# mailbox.net
KiCad netlist of a schematic drawn in EAGLE
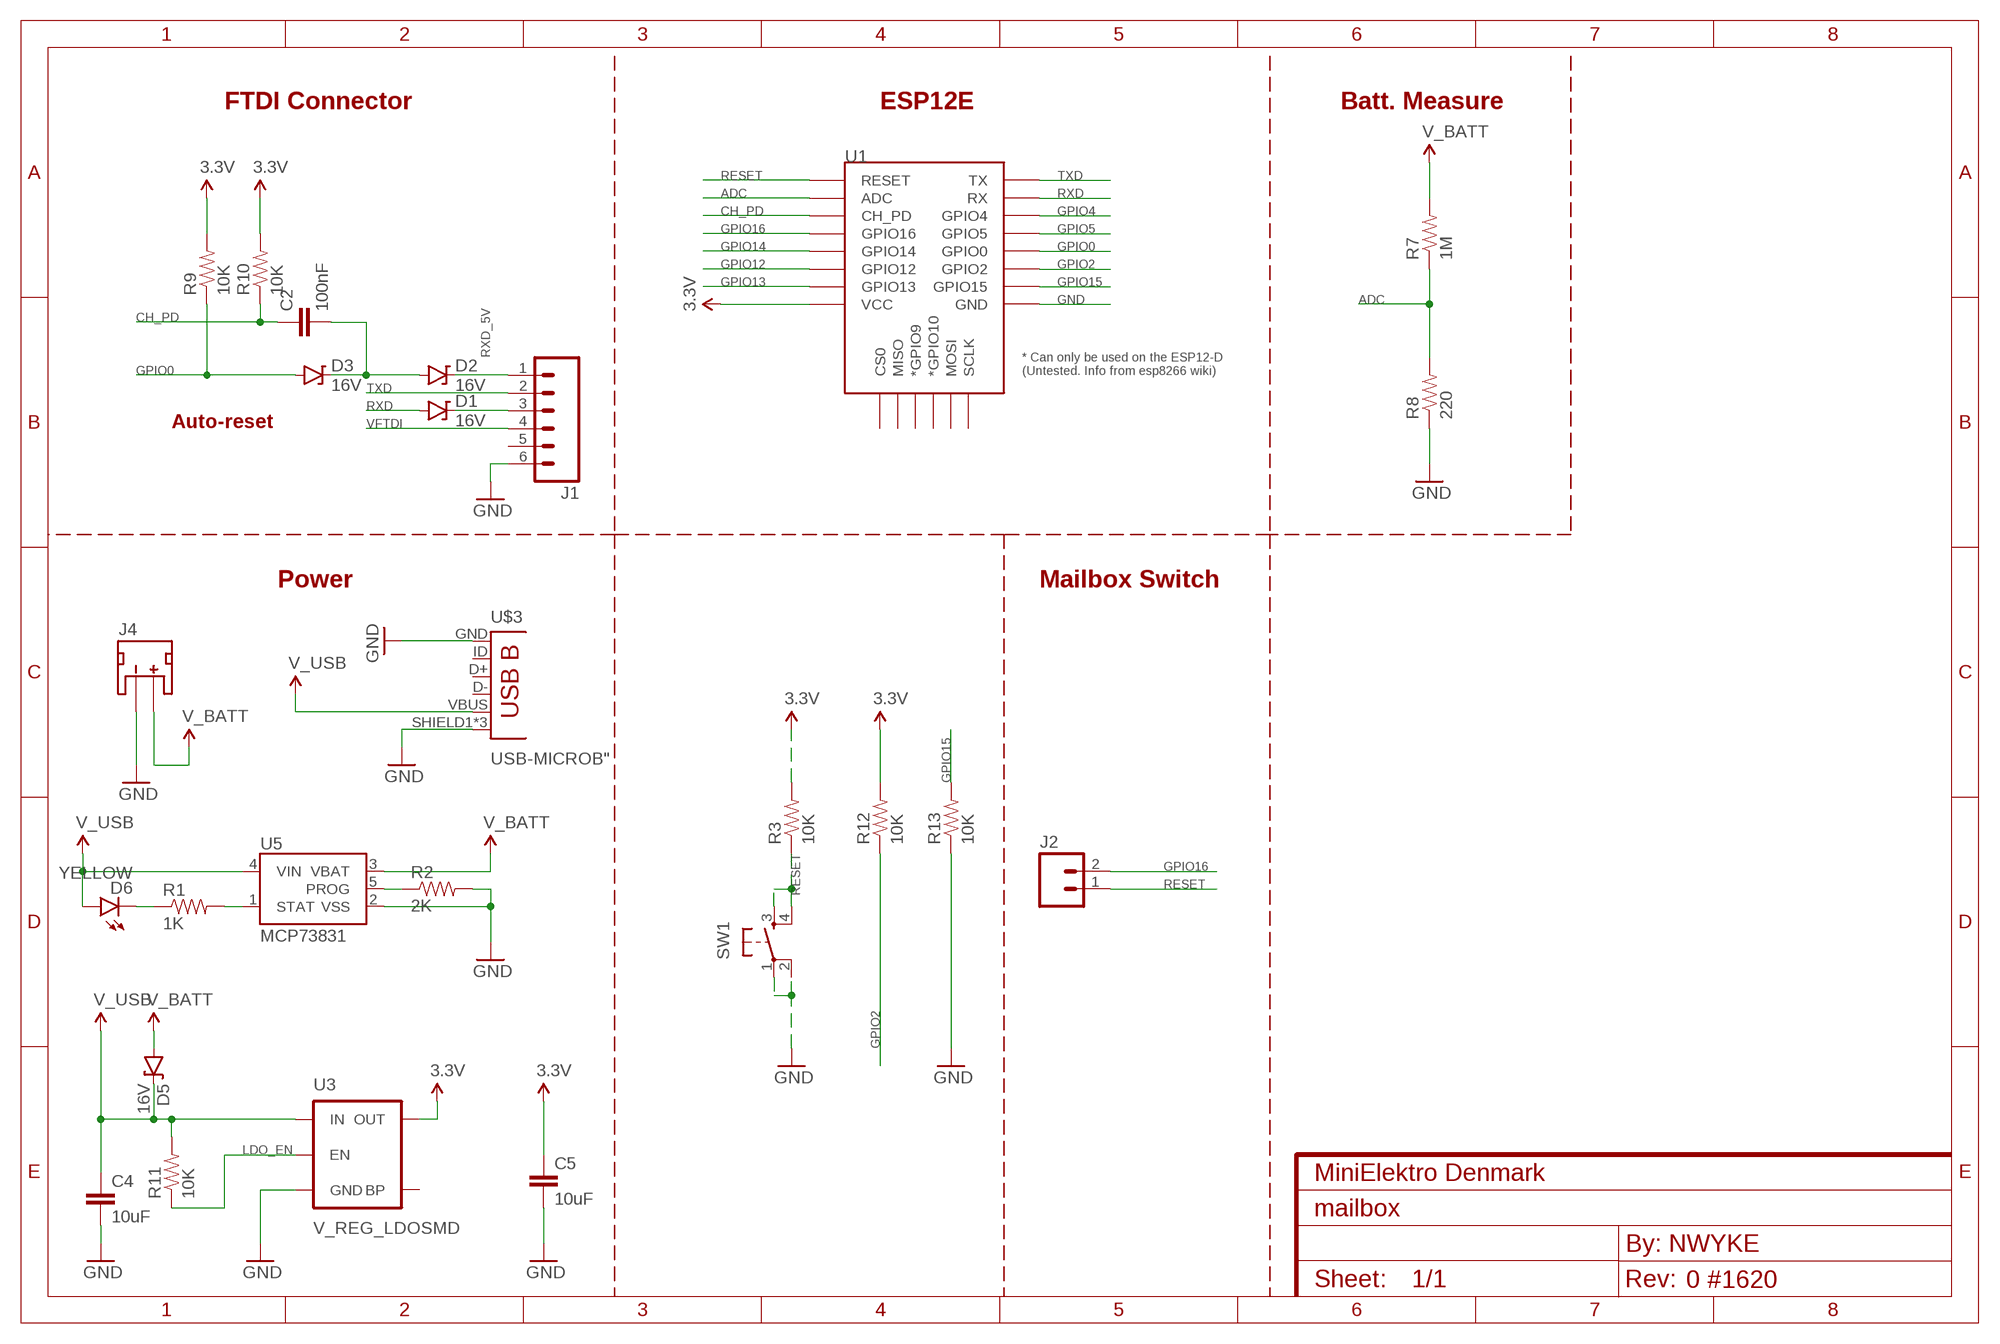
[diagram p0: schematic, sheet 1]

(export (version "E")
  (design (tool "Eeschema 10.0.6"))
  (components
    (comp (ref "C2")
      (value "100nF")
      (footprint "eagle-import:1206")
      (libsource (lib "eagle-import") (part "CAP1206"))
    )
    (comp (ref "C4")
      (value "10uF")
      (footprint "eagle-import:1206")
      (libsource (lib "eagle-import") (part "CAP1206"))
    )
    (comp (ref "C5")
      (value "10uF")
      (footprint "eagle-import:1206")
      (libsource (lib "eagle-import") (part "CAP1206"))
    )
    (comp (ref "D1")
      (value "16V")
      (footprint "eagle-import:SOD-123")
      (libsource (lib "eagle-import") (part "DIODE-ZENER16V"))
    )
    (comp (ref "D2")
      (value "16V")
      (footprint "eagle-import:SOD-123")
      (libsource (lib "eagle-import") (part "DIODE-ZENER16V"))
    )
    (comp (ref "D3")
      (value "16V")
      (footprint "eagle-import:SOD-123")
      (libsource (lib "eagle-import") (part "DIODE-ZENER16V"))
    )
    (comp (ref "D5")
      (value "16V")
      (footprint "eagle-import:SOD-123")
      (libsource (lib "eagle-import") (part "DIODE-ZENER16V"))
    )
    (comp (ref "D6")
      (value "YELLOW")
      (footprint "eagle-import:LED-1206")
      (libsource (lib "eagle-import") (part "LED-YELLOW1206"))
    )
    (comp (ref "J1")
      (value "M06SILK_FEMALE_PTH")
      (footprint "eagle-import:1X06")
      (libsource (lib "eagle-import") (part "M06SILK_FEMALE_PTH"))
    )
    (comp (ref "J2")
      (value "M02LOCK")
      (footprint "eagle-import:1X02_LOCK")
      (libsource (lib "eagle-import") (part "M02LOCK"))
    )
    (comp (ref "J4")
      (value "JST_2MM_MALE")
      (footprint "eagle-import:JST-2-SMD")
      (libsource (lib "eagle-import") (part "JST_2MM_MALE"))
    )
    (comp (ref "R1")
      (value "1K")
      (footprint "eagle-import:1206")
      (libsource (lib "eagle-import") (part "RESISTOR1206"))
    )
    (comp (ref "R2")
      (value "2K")
      (footprint "eagle-import:1206")
      (libsource (lib "eagle-import") (part "RESISTOR1206"))
    )
    (comp (ref "R3")
      (value "10K")
      (footprint "eagle-import:1206")
      (libsource (lib "eagle-import") (part "RESISTOR1206"))
    )
    (comp (ref "R7")
      (value "1M")
      (footprint "eagle-import:1206")
      (libsource (lib "eagle-import") (part "RESISTOR1206"))
    )
    (comp (ref "R8")
      (value "220")
      (footprint "eagle-import:1206")
      (libsource (lib "eagle-import") (part "RESISTOR1206"))
    )
    (comp (ref "R9")
      (value "10K")
      (footprint "eagle-import:1206")
      (libsource (lib "eagle-import") (part "RESISTOR1206"))
    )
    (comp (ref "R10")
      (value "10K")
      (footprint "eagle-import:1206")
      (libsource (lib "eagle-import") (part "RESISTOR1206"))
    )
    (comp (ref "R11")
      (value "10K")
      (footprint "eagle-import:1206")
      (libsource (lib "eagle-import") (part "RESISTOR1206"))
    )
    (comp (ref "R12")
      (value "10K")
      (footprint "eagle-import:1206")
      (libsource (lib "eagle-import") (part "RESISTOR1206"))
    )
    (comp (ref "R13")
      (value "10K")
      (footprint "eagle-import:1206")
      (libsource (lib "eagle-import") (part "RESISTOR1206"))
    )
    (comp (ref "SW1")
      (value "SWITCH_SPST_4_PINRECT")
      (footprint "eagle-import:TACTILE_SWITCH_SMD_4.6X2.8MM")
      (libsource (lib "eagle-import") (part "SWITCH_SPST_4_PINRECT"))
    )
    (comp (ref "U$3")
      (value "USB-MICROB\"")
      (footprint "eagle-import:USB-B-MICRO-SMD_V03")
      (libsource (lib "eagle-import") (part "USB-MICROB{dblquote}"))
    )
    (comp (ref "U1")
      (value "ESP12ESMD")
      (footprint "eagle-import:ESP12E-SMD")
      (libsource (lib "eagle-import") (part "ESP12ESMD"))
    )
    (comp (ref "U3")
      (value "V_REG_LDOSMD")
      (footprint "eagle-import:SOT23-5")
      (libsource (lib "eagle-import") (part "V_REG_LDOSMD"))
    )
    (comp (ref "U5")
      (value "MCP73831")
      (footprint "eagle-import:SOT23-5")
      (libsource (lib "eagle-import") (part "MCP73831"))
    )
  )
  (nets
    (net (code "1") (name "/ADC") (class "Default")
      (node (ref "R7") (pin "1") (pinfunction "1_1") (pintype "passive"))
      (node (ref "R8") (pin "2") (pinfunction "2_2") (pintype "passive"))
      (node (ref "U1") (pin "ADC") (pinfunction "ADC_ADC") (pintype "bidirectional"))
    )
    (net (code "2") (name "/CH_PD") (class "Default")
      (node (ref "C2") (pin "1") (pinfunction "1_1") (pintype "passive"))
      (node (ref "R10") (pin "1") (pinfunction "1_1") (pintype "passive"))
      (node (ref "U1") (pin "CH_PD") (pinfunction "CH_PD_CH_PD") (pintype "bidirectional"))
    )
    (net (code "3") (name "/GPIO0") (class "Default")
      (node (ref "D3") (pin "A") (pinfunction "A_A") (pintype "passive"))
      (node (ref "R9") (pin "1") (pinfunction "1_1") (pintype "passive"))
      (node (ref "U1") (pin "GPIO0") (pinfunction "GPIO0_GPIO0") (pintype "bidirectional"))
    )
    (net (code "4") (name "/GPIO2") (class "Default")
      (node (ref "R12") (pin "1") (pinfunction "1_1") (pintype "passive"))
      (node (ref "U1") (pin "GPIO2") (pinfunction "GPIO2_GPIO2") (pintype "bidirectional"))
    )
    (net (code "5") (name "/GPIO4") (class "Default")
      (node (ref "U1") (pin "GPIO4") (pinfunction "GPIO4_GPIO4") (pintype "bidirectional"))
    )
    (net (code "6") (name "/GPIO5") (class "Default")
      (node (ref "U1") (pin "GPIO5") (pinfunction "GPIO5_GPIO5") (pintype "bidirectional"))
    )
    (net (code "7") (name "/GPIO12") (class "Default")
      (node (ref "U1") (pin "GPIO12") (pinfunction "GPIO12_GPIO12") (pintype "bidirectional"))
    )
    (net (code "8") (name "/GPIO13") (class "Default")
      (node (ref "U1") (pin "GPIO13") (pinfunction "GPIO13_GPIO13") (pintype "bidirectional"))
    )
    (net (code "9") (name "/GPIO14") (class "Default")
      (node (ref "U1") (pin "GPIO14") (pinfunction "GPIO14_GPIO14") (pintype "bidirectional"))
    )
    (net (code "10") (name "/GPIO15") (class "Default")
      (node (ref "R13") (pin "2") (pinfunction "2_2") (pintype "passive"))
      (node (ref "U1") (pin "GPIO15") (pinfunction "GPIO15_GPIO15") (pintype "bidirectional"))
    )
    (net (code "11") (name "/GPIO16") (class "Default")
      (node (ref "J2") (pin "2") (pinfunction "2_2") (pintype "passive"))
      (node (ref "U1") (pin "GPIO16") (pinfunction "GPIO16_GPIO16") (pintype "bidirectional"))
    )
    (net (code "12") (name "/LDO_EN") (class "Default")
      (node (ref "R11") (pin "1") (pinfunction "1_1") (pintype "passive"))
      (node (ref "U3") (pin "3") (pinfunction "EN_3") (pintype "input"))
    )
    (net (code "13") (name "/RESET") (class "Default")
      (node (ref "J2") (pin "1") (pinfunction "1_1") (pintype "passive"))
      (node (ref "R3") (pin "1") (pinfunction "1_1") (pintype "passive"))
      (node (ref "SW1") (pin "3") (pinfunction "3_3") (pintype "passive"))
      (node (ref "SW1") (pin "4") (pinfunction "4_4") (pintype "passive"))
      (node (ref "U1") (pin "RESET") (pinfunction "RESET_RESET") (pintype "bidirectional"))
    )
    (net (code "14") (name "/RXD") (class "Default")
      (node (ref "D1") (pin "A") (pinfunction "A_A") (pintype "passive"))
      (node (ref "U1") (pin "RXD0") (pinfunction "RX_RXD0") (pintype "bidirectional"))
    )
    (net (code "15") (name "/RXD_5V") (class "Default")
      (node (ref "D1") (pin "C") (pinfunction "C_C") (pintype "passive"))
      (node (ref "J1") (pin "3") (pinfunction "3_3") (pintype "passive"))
    )
    (net (code "16") (name "/TXD") (class "Default")
      (node (ref "J1") (pin "2") (pinfunction "2_2") (pintype "passive"))
      (node (ref "U1") (pin "TXD0") (pinfunction "TX_TXD0") (pintype "bidirectional"))
    )
    (net (code "17") (name "/VFTDI") (class "Default")
      (node (ref "J1") (pin "4") (pinfunction "4_4") (pintype "passive"))
    )
    (net (code "18") (name "3.3V") (class "Default")
      (node (ref "C5") (pin "1") (pinfunction "1_1") (pintype "passive"))
      (node (ref "R10") (pin "2") (pinfunction "2_2") (pintype "passive"))
      (node (ref "R12") (pin "2") (pinfunction "2_2") (pintype "passive"))
      (node (ref "R3") (pin "2") (pinfunction "2_2") (pintype "passive"))
      (node (ref "R9") (pin "2") (pinfunction "2_2") (pintype "passive"))
      (node (ref "U1") (pin "VCC") (pinfunction "VCC_VCC") (pintype "bidirectional"))
      (node (ref "U3") (pin "5") (pinfunction "OUT_5") (pintype "passive"))
    )
    (net (code "19") (name "GND") (class "Default")
      (node (ref "C4") (pin "2") (pinfunction "2_2") (pintype "passive"))
      (node (ref "C5") (pin "2") (pinfunction "2_2") (pintype "passive"))
      (node (ref "J1") (pin "6") (pinfunction "6_6") (pintype "passive"))
      (node (ref "J4") (pin "1") (pinfunction "-_1") (pintype "bidirectional"))
      (node (ref "R13") (pin "1") (pinfunction "1_1") (pintype "passive"))
      (node (ref "R2") (pin "2") (pinfunction "2_2") (pintype "passive"))
      (node (ref "R8") (pin "1") (pinfunction "1_1") (pintype "passive"))
      (node (ref "SW1") (pin "1") (pinfunction "1_1") (pintype "passive"))
      (node (ref "SW1") (pin "2") (pinfunction "2_2") (pintype "passive"))
      (node (ref "U$3") (pin "GND") (pinfunction "GND_GND") (pintype "bidirectional"))
      (node (ref "U$3") (pin "SHIELD1") (pinfunction "SHIELD_SHIELD1") (pintype "bidirectional"))
      (node (ref "U$3") (pin "SHIELD2") (pinfunction "SHIELD_SHIELD2") (pintype "bidirectional"))
      (node (ref "U$3") (pin "SHIELD3") (pinfunction "SHIELD_SHIELD3") (pintype "bidirectional"))
      (node (ref "U1") (pin "GND") (pinfunction "GND_GND") (pintype "bidirectional"))
      (node (ref "U3") (pin "2") (pinfunction "GND_2") (pintype "input"))
      (node (ref "U5") (pin "2") (pinfunction "VSS_2") (pintype "power_in"))
    )
    (net (code "20") (name "Net-(C2-Pad2)") (class "Default")
      (node (ref "C2") (pin "2") (pinfunction "2_2") (pintype "passive"))
      (node (ref "D2") (pin "A") (pinfunction "A_A") (pintype "passive"))
      (node (ref "D3") (pin "C") (pinfunction "C_C") (pintype "passive"))
    )
    (net (code "21") (name "Net-(D2-PadC)") (class "Default")
      (node (ref "D2") (pin "C") (pinfunction "C_C") (pintype "passive"))
      (node (ref "J1") (pin "1") (pinfunction "1_1") (pintype "passive"))
    )
    (net (code "22") (name "Net-(D6-PadC)") (class "Default")
      (node (ref "D6") (pin "C") (pinfunction "C_C") (pintype "passive"))
      (node (ref "R1") (pin "1") (pinfunction "1_1") (pintype "passive"))
    )
    (net (code "23") (name "Net-(U5-PROG)") (class "Default")
      (node (ref "R2") (pin "1") (pinfunction "1_1") (pintype "passive"))
      (node (ref "U5") (pin "5") (pinfunction "PROG_5") (pintype "input"))
    )
    (net (code "24") (name "Net-(U5-STAT)") (class "Default")
      (node (ref "R1") (pin "2") (pinfunction "2_2") (pintype "passive"))
      (node (ref "U5") (pin "1") (pinfunction "STAT_1") (pintype "output"))
    )
    (net (code "25") (name "V_BATT") (class "Default")
      (node (ref "D5") (pin "A") (pinfunction "A_A") (pintype "passive"))
      (node (ref "J4") (pin "2") (pinfunction "+_2") (pintype "bidirectional"))
      (node (ref "R7") (pin "2") (pinfunction "2_2") (pintype "passive"))
      (node (ref "U5") (pin "3") (pinfunction "VBAT_3") (pintype "power_in"))
    )
    (net (code "26") (name "V_USB") (class "Default")
      (node (ref "C4") (pin "1") (pinfunction "1_1") (pintype "passive"))
      (node (ref "D5") (pin "C") (pinfunction "C_C") (pintype "passive"))
      (node (ref "D6") (pin "A") (pinfunction "A_A") (pintype "passive"))
      (node (ref "R11") (pin "2") (pinfunction "2_2") (pintype "passive"))
      (node (ref "U$3") (pin "VBUS") (pinfunction "VBUS_VBUS") (pintype "bidirectional"))
      (node (ref "U3") (pin "1") (pinfunction "IN_1") (pintype "input"))
      (node (ref "U5") (pin "4") (pinfunction "VIN_4") (pintype "power_in"))
    )
    (net (code "27") (name "unconnected-(J1-Pad5)") (class "Default")
      (node (ref "J1") (pin "5") (pinfunction "5_5") (pintype "passive"))
    )
    (net (code "28") (name "unconnected-(J4-PAD1-PadNC1)") (class "Default")
      (node (ref "J4") (pin "NC1") (pinfunction "PAD1_NC1") (pintype "bidirectional"))
    )
    (net (code "29") (name "unconnected-(J4-PAD2-PadNC2)") (class "Default")
      (node (ref "J4") (pin "NC2") (pinfunction "PAD2_NC2") (pintype "bidirectional"))
    )
    (net (code "30") (name "unconnected-(U$3-PadD+)") (class "Default")
      (node (ref "U$3") (pin "D+") (pinfunction "D+_D+") (pintype "bidirectional"))
    )
    (net (code "31") (name "unconnected-(U$3-PadD-)") (class "Default")
      (node (ref "U$3") (pin "D-") (pinfunction "D-_D-") (pintype "bidirectional"))
    )
    (net (code "32") (name "unconnected-(U$3-USBID-PadID)") (class "Default")
      (node (ref "U$3") (pin "ID") (pinfunction "USBID_ID") (pintype "bidirectional"))
    )
    (net (code "33") (name "unconnected-(U1-*GPIO9-PadGPIO9)") (class "Default")
      (node (ref "U1") (pin "GPIO9") (pinfunction "*GPIO9_GPIO9") (pintype "bidirectional"))
    )
    (net (code "34") (name "unconnected-(U1-*GPIO10-PadGPIO10)") (class "Default")
      (node (ref "U1") (pin "GPIO10") (pinfunction "*GPIO10_GPIO10") (pintype "bidirectional"))
    )
    (net (code "35") (name "unconnected-(U1-PadCS0)") (class "Default")
      (node (ref "U1") (pin "CS0") (pinfunction "CS0_CS0") (pintype "bidirectional"))
    )
    (net (code "36") (name "unconnected-(U1-PadMISO)") (class "Default")
      (node (ref "U1") (pin "MISO") (pinfunction "MISO_MISO") (pintype "bidirectional"))
    )
    (net (code "37") (name "unconnected-(U1-PadMOSI)") (class "Default")
      (node (ref "U1") (pin "MOSI") (pinfunction "MOSI_MOSI") (pintype "bidirectional"))
    )
    (net (code "38") (name "unconnected-(U1-PadSCLK)") (class "Default")
      (node (ref "U1") (pin "SCLK") (pinfunction "SCLK_SCLK") (pintype "bidirectional"))
    )
    (net (code "39") (name "unconnected-(U3-BP-Pad4)") (class "Default")
      (node (ref "U3") (pin "4") (pinfunction "BP_4") (pintype "input"))
    )
  )
)
